# RelayOutputs.net
KiCad netlist of a schematic drawn in Altium Designer
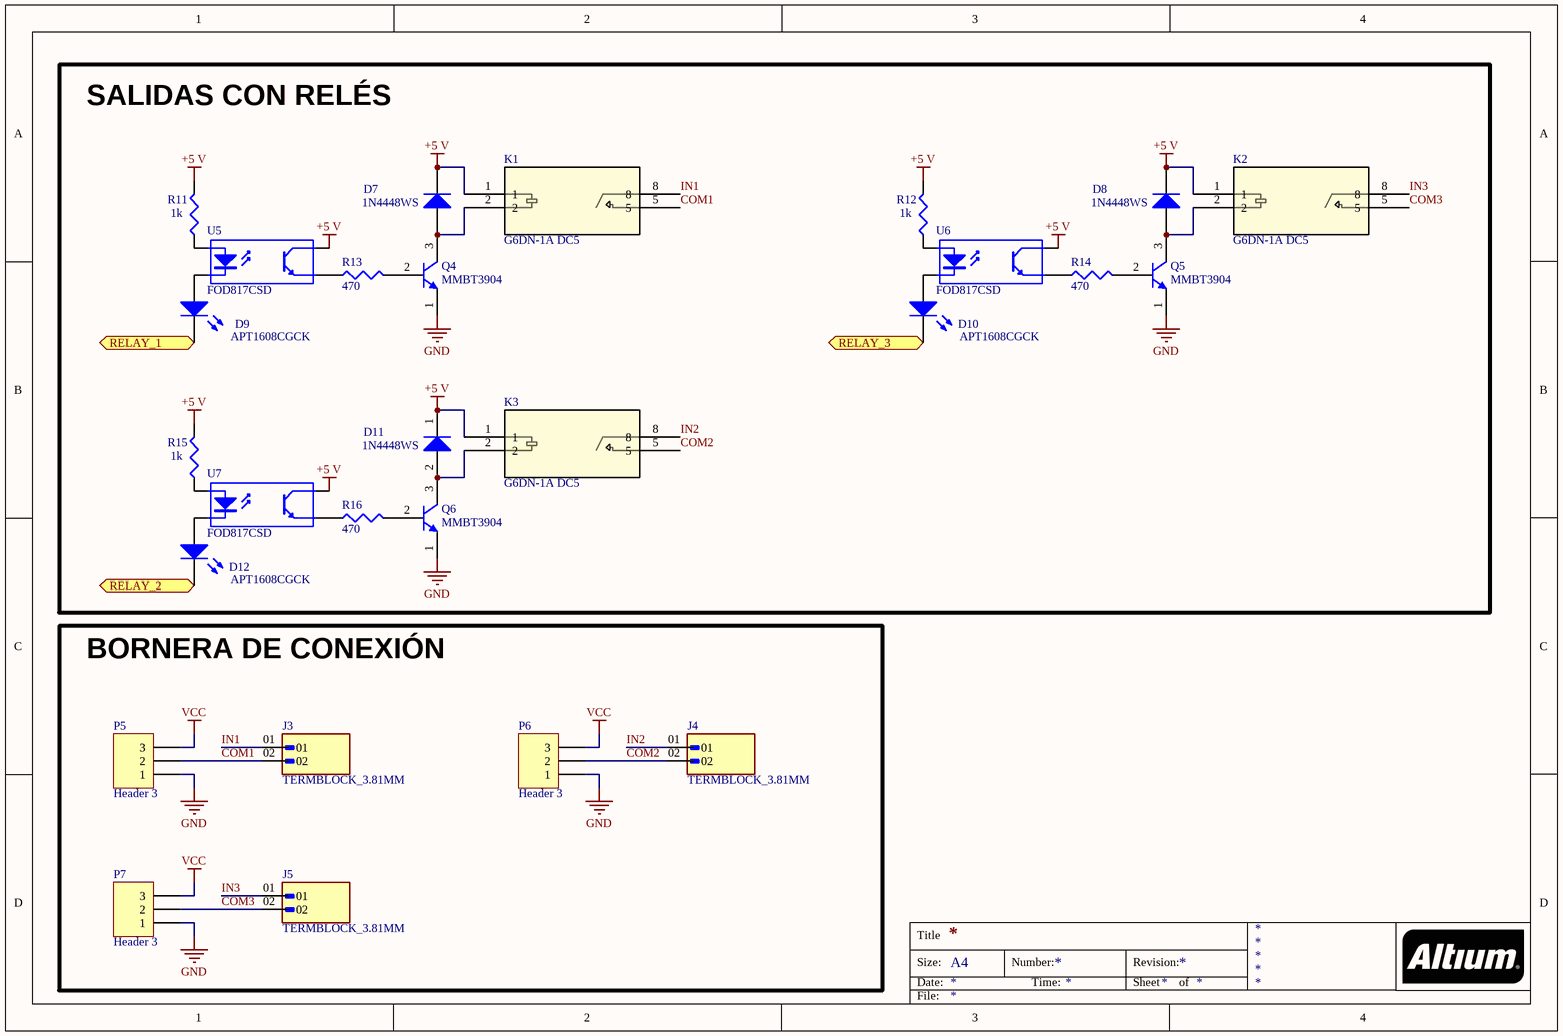
[diagram p0: RelayOutputs.SchDoc]

(export (version "E")
  (design (tool "Eeschema 10.0.6"))
  (components
    (comp (ref "D7")
      (value "1N4448WS")
      (footprint "SOD-323")
      (description "Default Diode")
      (fields (field (name "PUBLISHER") "Altium Limited"))
      (libsource (lib "Miscellaneous Devices") (part "Diode"))
    )
    (comp (ref "D8")
      (value "1N4448WS")
      (footprint "SOD-323")
      (description "Default Diode")
      (fields (field (name "PUBLISHER") "Altium Limited"))
      (libsource (lib "Miscellaneous Devices") (part "Diode"))
    )
    (comp (ref "D9")
      (value "APT1608CGCK")
      (footprint "ChipDiode1608")
      (description "LED 1.6x0.8 mm 570 nm GRN CLR SMD")
      (fields (field (name "PUBLISHER") "Altium Limited"))
      (libsource (lib "Miscellaneous Devices") (part "LED2"))
    )
    (comp (ref "D10")
      (value "APT1608CGCK")
      (footprint "ChipDiode1608")
      (description "LED 1.6x0.8 mm 570 nm GRN CLR SMD")
      (fields (field (name "PUBLISHER") "Altium Limited"))
      (libsource (lib "Miscellaneous Devices") (part "LED2"))
    )
    (comp (ref "D11")
      (value "1N4448WS")
      (footprint "SOD-323")
      (description "Default Diode")
      (fields (field (name "PUBLISHER") "Altium Limited"))
      (libsource (lib "") (part "Diode_1"))
    )
    (comp (ref "D12")
      (value "APT1608CGCK")
      (footprint "ChipDiode1608")
      (description "LED 1.6x0.8 mm 570 nm GRN CLR SMD")
      (fields (field (name "PUBLISHER") "Altium Limited"))
      (libsource (lib "Miscellaneous Devices") (part "LED2"))
    )
    (comp (ref "J3")
      (value "TERMBLOCK_3.81MM")
      (footprint "TERMBLOCK_3.81MM_90DEG_2POS")
      (description "TERMBLOCK_3.81MM_90DEG_2POS (DigiKey: 1803277)")
      (libsource (lib "MH_Lib") (part "TERMBLOCK_3.81MM_90DEG_2POS"))
    )
    (comp (ref "J4")
      (value "TERMBLOCK_3.81MM")
      (footprint "TERMBLOCK_3.81MM_90DEG_2POS")
      (description "TERMBLOCK_3.81MM_90DEG_2POS (DigiKey: 1803277)")
      (libsource (lib "MH_Lib") (part "TERMBLOCK_3.81MM_90DEG_2POS"))
    )
    (comp (ref "J5")
      (value "TERMBLOCK_3.81MM")
      (footprint "TERMBLOCK_3.81MM_90DEG_2POS")
      (description "TERMBLOCK_3.81MM_90DEG_2POS (DigiKey: 1803277)")
      (libsource (lib "MH_Lib") (part "TERMBLOCK_3.81MM_90DEG_2POS"))
    )
    (comp (ref "K1")
      (value "G6DN-1A DC5")
      (footprint "RELAY_G6DN-1A_OMR")
      (description "Rele_Omron_5V_5A")
      (libsource (lib "Adox_Lib") (part "G6DN-1A DC5"))
    )
    (comp (ref "K2")
      (value "G6DN-1A DC5")
      (footprint "RELAY_G6DN-1A_OMR")
      (description "Rele_Omron_5V_5A")
      (libsource (lib "Adox_Lib") (part "G6DN-1A DC5"))
    )
    (comp (ref "K3")
      (value "G6DN-1A DC5")
      (footprint "RELAY_G6DN-1A_OMR")
      (description "Rele_Omron_5V_5A")
      (libsource (lib "Adox_Lib") (part "G6DN-1A DC5"))
    )
    (comp (ref "P5")
      (value "Header 3")
      (footprint "MH_Miscellaneous_Devices_Pcblib:CONNHDR_1X3_2.54MM")
      (description "Header, 3-Pin")
      (fields (field (name "PUBLISHER") "Altium Limited"))
      (libsource (lib "Miscellaneous Connectors") (part "Header 3"))
    )
    (comp (ref "P6")
      (value "Header 3")
      (footprint "MH_Miscellaneous_Devices_Pcblib:CONNHDR_1X3_2.54MM")
      (description "Header, 3-Pin")
      (fields (field (name "PUBLISHER") "Altium Limited"))
      (libsource (lib "Miscellaneous Connectors") (part "Header 3"))
    )
    (comp (ref "P7")
      (value "Header 3")
      (footprint "MH_Miscellaneous_Devices_Pcblib:CONNHDR_1X3_2.54MM")
      (description "Header, 3-Pin")
      (fields (field (name "PUBLISHER") "Altium Limited"))
      (libsource (lib "Miscellaneous Connectors") (part "Header 3"))
    )
    (comp (ref "Q4")
      (value "MMBT3904")
      (footprint "MMBT3904")
      (description "TRANS NPN 40V 0.2A SOT-23-3")
      (libsource (lib "MH_Lib") (part "MMBT3904"))
    )
    (comp (ref "Q5")
      (value "MMBT3904")
      (footprint "MMBT3904")
      (description "TRANS NPN 40V 0.2A SOT-23-3")
      (libsource (lib "MH_Lib") (part "MMBT3904"))
    )
    (comp (ref "Q6")
      (value "MMBT3904")
      (footprint "MMBT3904")
      (description "TRANS NPN 40V 0.2A SOT-23-3")
      (libsource (lib "MH_Lib") (part "MMBT3904"))
    )
    (comp (ref "R11")
      (value "1k")
      (footprint "RESC2012N")
      (description "Resistor")
      (fields (field (name "PUBLISHER") "Altium Limited"))
      (libsource (lib "Miscellaneous Devices") (part "Res3"))
    )
    (comp (ref "R12")
      (value "1k")
      (footprint "RESC2012N")
      (description "Resistor")
      (fields (field (name "PUBLISHER") "Altium Limited"))
      (libsource (lib "Miscellaneous Devices") (part "Res3"))
    )
    (comp (ref "R13")
      (value "470")
      (footprint "RESC2012N")
      (description "Resistor")
      (fields (field (name "PUBLISHER") "Altium Limited"))
      (libsource (lib "Miscellaneous Devices") (part "Res3"))
    )
    (comp (ref "R14")
      (value "470")
      (footprint "RESC2012N")
      (description "Resistor")
      (fields (field (name "PUBLISHER") "Altium Limited"))
      (libsource (lib "Miscellaneous Devices") (part "Res3"))
    )
    (comp (ref "R15")
      (value "1k")
      (footprint "RESC2012N")
      (description "Resistor")
      (fields (field (name "PUBLISHER") "Altium Limited"))
      (libsource (lib "Miscellaneous Devices") (part "Res3"))
    )
    (comp (ref "R16")
      (value "470")
      (footprint "RESC2012N")
      (description "Resistor")
      (fields (field (name "PUBLISHER") "Altium Limited"))
      (libsource (lib "Miscellaneous Devices") (part "Res3"))
    )
    (comp (ref "U5")
      (value "FOD817CSD")
      (footprint "OPTOISOLATOR 5KV TRANSISTOR 4SMD")
      (description "4-Pin Phototransistor Optocoupler")
      (fields (field (name "PUBLISHER") "Altium Limited"))
      (libsource (lib "Miscellaneous Devices") (part "Optoisolator1"))
    )
    (comp (ref "U6")
      (value "FOD817CSD")
      (footprint "OPTOISOLATOR 5KV TRANSISTOR 4SMD")
      (description "4-Pin Phototransistor Optocoupler")
      (fields (field (name "PUBLISHER") "Altium Limited"))
      (libsource (lib "Miscellaneous Devices") (part "Optoisolator1"))
    )
    (comp (ref "U7")
      (value "FOD817CSD")
      (footprint "OPTOISOLATOR 5KV TRANSISTOR 4SMD")
      (description "4-Pin Phototransistor Optocoupler")
      (fields (field (name "PUBLISHER") "Altium Limited"))
      (libsource (lib "Miscellaneous Devices") (part "Optoisolator1"))
    )
  )
  (nets
    (net (code "1") (name "+5 V") (class "Default")
      (node (ref "D11") (pin "1") (pinfunction "K_1") (pintype "passive"))
      (node (ref "D7") (pin "1") (pinfunction "K_1") (pintype "passive"))
      (node (ref "D8") (pin "1") (pinfunction "K_1") (pintype "passive"))
      (node (ref "K1") (pin "1") (pinfunction "1_1") (pintype "passive"))
      (node (ref "K2") (pin "1") (pinfunction "1_1") (pintype "passive"))
      (node (ref "K3") (pin "1") (pinfunction "1_1") (pintype "passive"))
      (node (ref "R11") (pin "2") (pinfunction "2_2") (pintype "passive"))
      (node (ref "R12") (pin "2") (pinfunction "2_2") (pintype "passive"))
      (node (ref "R15") (pin "2") (pinfunction "2_2") (pintype "passive"))
      (node (ref "U5") (pin "4") (pinfunction "C_4") (pintype "passive"))
      (node (ref "U6") (pin "4") (pinfunction "C_4") (pintype "passive"))
      (node (ref "U7") (pin "4") (pinfunction "C_4") (pintype "passive"))
    )
    (net (code "2") (name "/COM1") (class "Default")
      (node (ref "J3") (pin "02") (pinfunction "02_02") (pintype "passive"))
      (node (ref "K1") (pin "5") (pinfunction "5_5") (pintype "passive"))
      (node (ref "P5") (pin "2") (pinfunction "2_2") (pintype "passive"))
    )
    (net (code "3") (name "/COM2") (class "Default")
      (node (ref "J4") (pin "02") (pinfunction "02_02") (pintype "passive"))
      (node (ref "K3") (pin "5") (pinfunction "5_5") (pintype "passive"))
      (node (ref "P6") (pin "2") (pinfunction "2_2") (pintype "passive"))
    )
    (net (code "4") (name "/COM3") (class "Default")
      (node (ref "J5") (pin "02") (pinfunction "02_02") (pintype "passive"))
      (node (ref "K2") (pin "5") (pinfunction "5_5") (pintype "passive"))
      (node (ref "P7") (pin "2") (pinfunction "2_2") (pintype "passive"))
    )
    (net (code "5") (name "/IN1") (class "Default")
      (node (ref "J3") (pin "01") (pinfunction "01_01") (pintype "passive"))
      (node (ref "K1") (pin "8") (pinfunction "8_8") (pintype "passive"))
    )
    (net (code "6") (name "/IN2") (class "Default")
      (node (ref "J4") (pin "01") (pinfunction "01_01") (pintype "passive"))
      (node (ref "K3") (pin "8") (pinfunction "8_8") (pintype "passive"))
    )
    (net (code "7") (name "/IN3") (class "Default")
      (node (ref "J5") (pin "01") (pinfunction "01_01") (pintype "passive"))
      (node (ref "K2") (pin "8") (pinfunction "8_8") (pintype "passive"))
    )
    (net (code "8") (name "/RELAY_1") (class "Default")
      (node (ref "D9") (pin "2") (pinfunction "K_2") (pintype "passive"))
    )
    (net (code "9") (name "/RELAY_2") (class "Default")
      (node (ref "D12") (pin "2") (pinfunction "K_2") (pintype "passive"))
    )
    (net (code "10") (name "/RELAY_3") (class "Default")
      (node (ref "D10") (pin "2") (pinfunction "K_2") (pintype "passive"))
    )
    (net (code "11") (name "GND") (class "Default")
      (node (ref "P5") (pin "1") (pinfunction "1_1") (pintype "passive"))
      (node (ref "P6") (pin "1") (pinfunction "1_1") (pintype "passive"))
      (node (ref "P7") (pin "1") (pinfunction "1_1") (pintype "passive"))
      (node (ref "Q4") (pin "1") (pinfunction "E_1") (pintype "passive"))
      (node (ref "Q5") (pin "1") (pinfunction "E_1") (pintype "passive"))
      (node (ref "Q6") (pin "1") (pinfunction "E_1") (pintype "passive"))
    )
    (net (code "12") (name "Net-(D7-A)") (class "Default")
      (node (ref "D7") (pin "2") (pinfunction "A_2") (pintype "passive"))
      (node (ref "K1") (pin "2") (pinfunction "2_2") (pintype "passive"))
      (node (ref "Q4") (pin "3") (pinfunction "C_3") (pintype "passive"))
    )
    (net (code "13") (name "Net-(D8-A)") (class "Default")
      (node (ref "D8") (pin "2") (pinfunction "A_2") (pintype "passive"))
      (node (ref "K2") (pin "2") (pinfunction "2_2") (pintype "passive"))
      (node (ref "Q5") (pin "3") (pinfunction "C_3") (pintype "passive"))
    )
    (net (code "14") (name "Net-(D9-A)") (class "Default")
      (node (ref "D9") (pin "1") (pinfunction "A_1") (pintype "passive"))
      (node (ref "U5") (pin "2") (pinfunction "K_2") (pintype "passive"))
    )
    (net (code "15") (name "Net-(D10-A)") (class "Default")
      (node (ref "D10") (pin "1") (pinfunction "A_1") (pintype "passive"))
      (node (ref "U6") (pin "2") (pinfunction "K_2") (pintype "passive"))
    )
    (net (code "16") (name "Net-(D11-A)") (class "Default")
      (node (ref "D11") (pin "2") (pinfunction "A_2") (pintype "passive"))
      (node (ref "K3") (pin "2") (pinfunction "2_2") (pintype "passive"))
      (node (ref "Q6") (pin "3") (pinfunction "C_3") (pintype "passive"))
    )
    (net (code "17") (name "Net-(D12-A)") (class "Default")
      (node (ref "D12") (pin "1") (pinfunction "A_1") (pintype "passive"))
      (node (ref "U7") (pin "2") (pinfunction "K_2") (pintype "passive"))
    )
    (net (code "18") (name "Net-(Q4-B)") (class "Default")
      (node (ref "Q4") (pin "2") (pinfunction "B_2") (pintype "passive"))
      (node (ref "R13") (pin "2") (pinfunction "2_2") (pintype "passive"))
    )
    (net (code "19") (name "Net-(Q5-B)") (class "Default")
      (node (ref "Q5") (pin "2") (pinfunction "B_2") (pintype "passive"))
      (node (ref "R14") (pin "2") (pinfunction "2_2") (pintype "passive"))
    )
    (net (code "20") (name "Net-(Q6-B)") (class "Default")
      (node (ref "Q6") (pin "2") (pinfunction "B_2") (pintype "passive"))
      (node (ref "R16") (pin "2") (pinfunction "2_2") (pintype "passive"))
    )
    (net (code "21") (name "Net-(U5-A)") (class "Default")
      (node (ref "R11") (pin "1") (pinfunction "1_1") (pintype "passive"))
      (node (ref "U5") (pin "1") (pinfunction "A_1") (pintype "passive"))
    )
    (net (code "22") (name "Net-(U5-E)") (class "Default")
      (node (ref "R13") (pin "1") (pinfunction "1_1") (pintype "passive"))
      (node (ref "U5") (pin "3") (pinfunction "E_3") (pintype "passive"))
    )
    (net (code "23") (name "Net-(U6-A)") (class "Default")
      (node (ref "R12") (pin "1") (pinfunction "1_1") (pintype "passive"))
      (node (ref "U6") (pin "1") (pinfunction "A_1") (pintype "passive"))
    )
    (net (code "24") (name "Net-(U6-E)") (class "Default")
      (node (ref "R14") (pin "1") (pinfunction "1_1") (pintype "passive"))
      (node (ref "U6") (pin "3") (pinfunction "E_3") (pintype "passive"))
    )
    (net (code "25") (name "Net-(U7-A)") (class "Default")
      (node (ref "R15") (pin "1") (pinfunction "1_1") (pintype "passive"))
      (node (ref "U7") (pin "1") (pinfunction "A_1") (pintype "passive"))
    )
    (net (code "26") (name "Net-(U7-E)") (class "Default")
      (node (ref "R16") (pin "1") (pinfunction "1_1") (pintype "passive"))
      (node (ref "U7") (pin "3") (pinfunction "E_3") (pintype "passive"))
    )
    (net (code "27") (name "VCC") (class "Default")
      (node (ref "P5") (pin "3") (pinfunction "3_3") (pintype "passive"))
      (node (ref "P6") (pin "3") (pinfunction "3_3") (pintype "passive"))
      (node (ref "P7") (pin "3") (pinfunction "3_3") (pintype "passive"))
    )
  )
)
